# PT4115-Driver.net
KiCad netlist of a schematic drawn in EAGLE
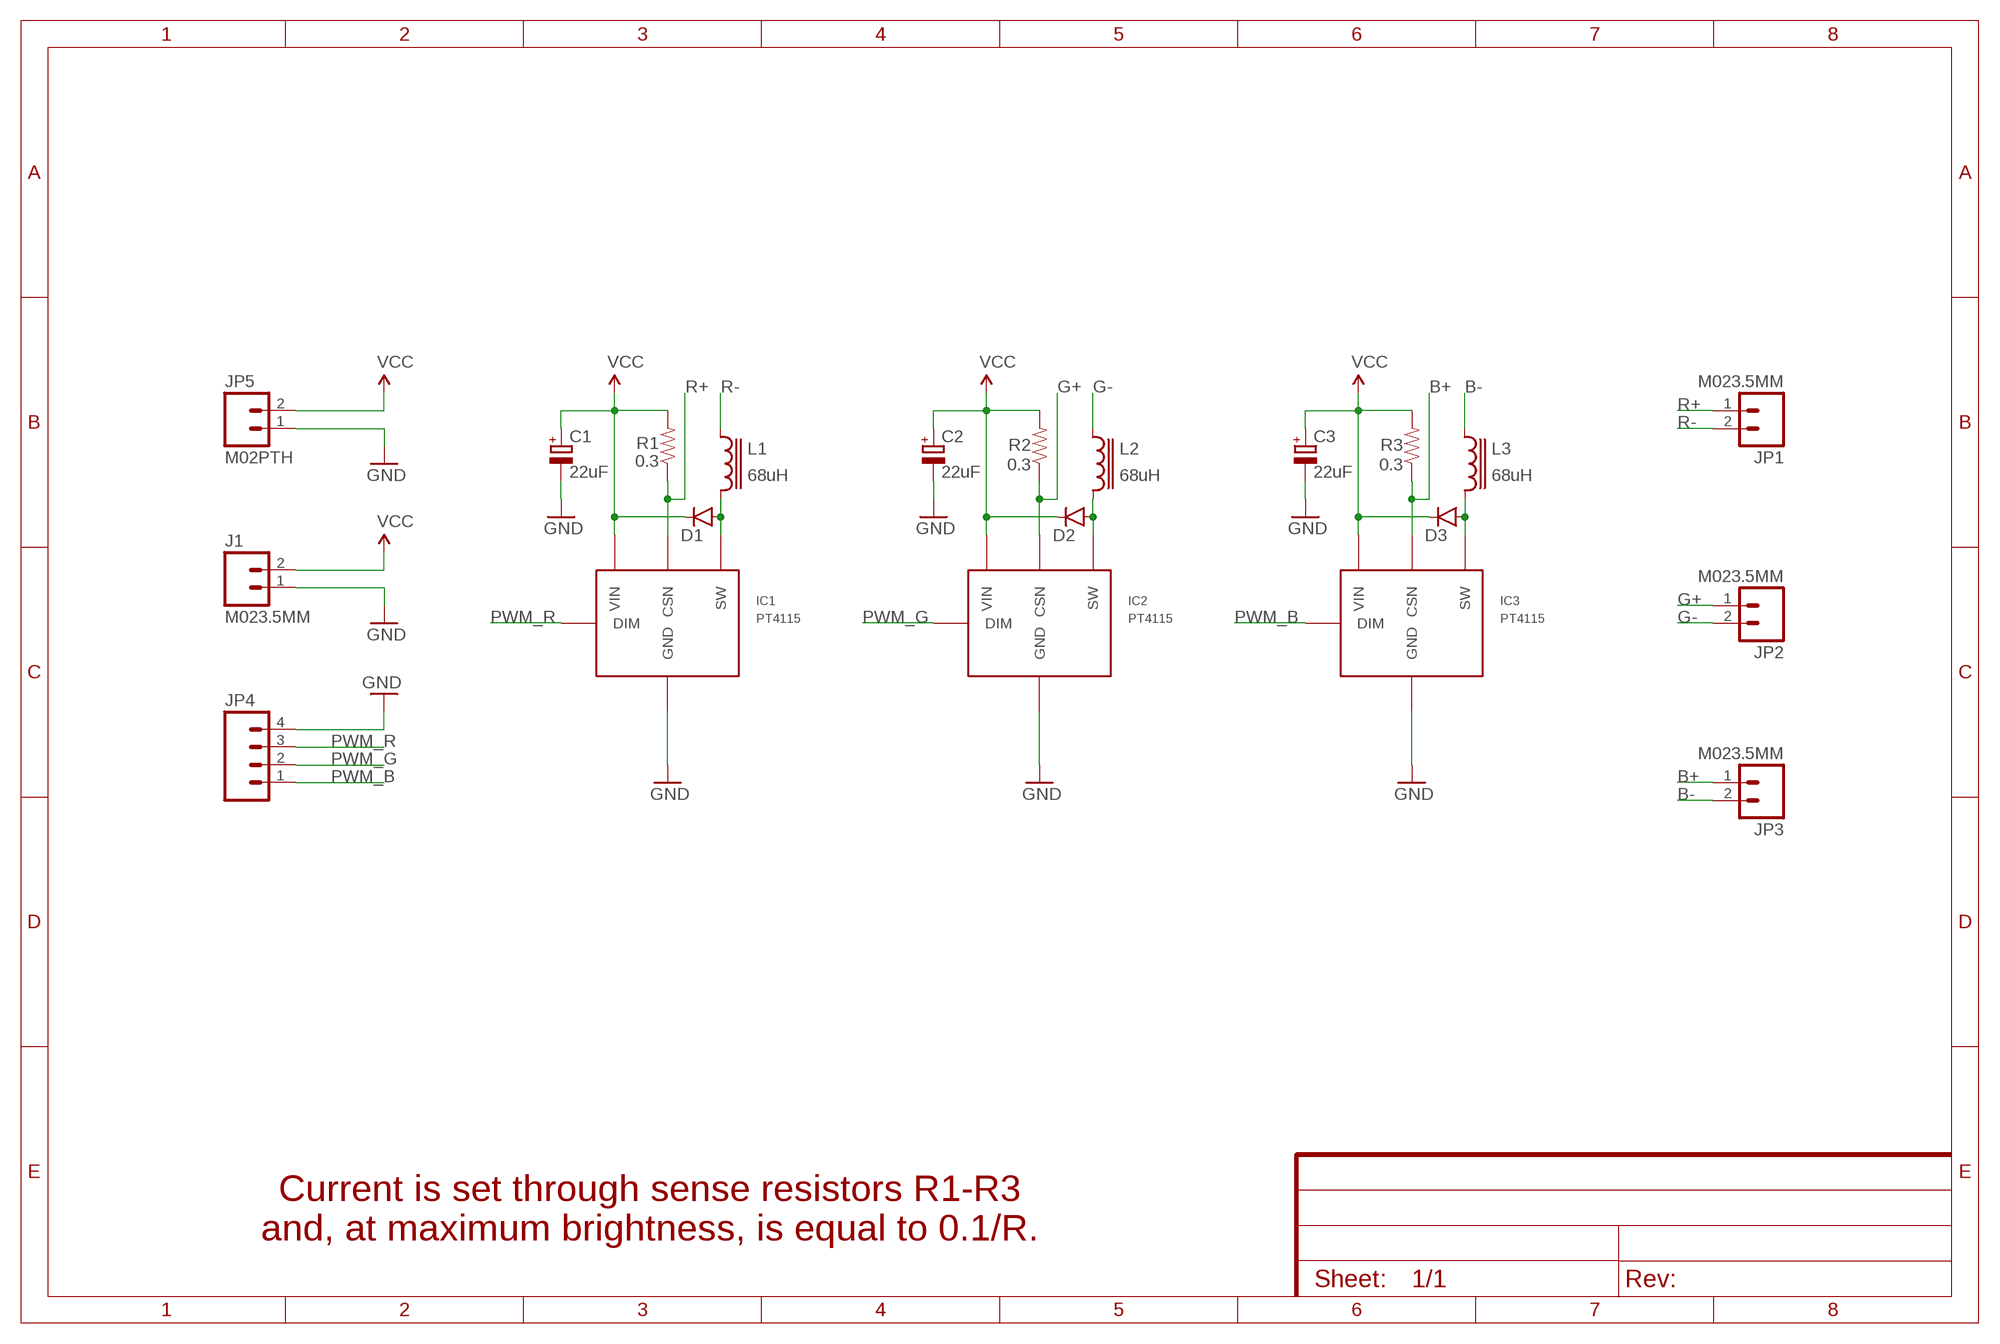
[diagram p0: schematic, sheet 1]

(export (version "E")
  (design (tool "Eeschema 10.0.6"))
  (components
    (comp (ref "C1")
      (value "22uF")
      (footprint "eagle-import:D_7343-31R")
      (libsource (lib "eagle-import") (part "CPOL-EUD/7343-31R"))
    )
    (comp (ref "C2")
      (value "22uF")
      (footprint "eagle-import:D_7343-31R")
      (libsource (lib "eagle-import") (part "CPOL-EUD/7343-31R"))
    )
    (comp (ref "C3")
      (value "22uF")
      (footprint "eagle-import:D_7343-31R")
      (libsource (lib "eagle-import") (part "CPOL-EUD/7343-31R"))
    )
    (comp (ref "D1")
      (value "DIODESMA-KIT")
      (footprint "eagle-import:SMA-DIODE-KIT")
      (libsource (lib "eagle-import") (part "DIODESMA-KIT"))
    )
    (comp (ref "D2")
      (value "DIODESMA-KIT")
      (footprint "eagle-import:SMA-DIODE-KIT")
      (libsource (lib "eagle-import") (part "DIODESMA-KIT"))
    )
    (comp (ref "D3")
      (value "DIODESMA-KIT")
      (footprint "eagle-import:SMA-DIODE-KIT")
      (libsource (lib "eagle-import") (part "DIODESMA-KIT"))
    )
    (comp (ref "IC1")
      (value "PT4115")
      (footprint "eagle-import:PT4115")
      (libsource (lib "eagle-import") (part "PT4115"))
    )
    (comp (ref "IC2")
      (value "PT4115")
      (footprint "eagle-import:PT4115")
      (libsource (lib "eagle-import") (part "PT4115"))
    )
    (comp (ref "IC3")
      (value "PT4115")
      (footprint "eagle-import:PT4115")
      (libsource (lib "eagle-import") (part "PT4115"))
    )
    (comp (ref "J1")
      (value "M023.5MM")
      (footprint "eagle-import:SCREWTERMINAL-3.5MM-2")
      (libsource (lib "eagle-import") (part "M023.5MM"))
    )
    (comp (ref "JP1")
      (value "M023.5MM")
      (footprint "eagle-import:SCREWTERMINAL-3.5MM-2")
      (libsource (lib "eagle-import") (part "M023.5MM"))
    )
    (comp (ref "JP2")
      (value "M023.5MM")
      (footprint "eagle-import:SCREWTERMINAL-3.5MM-2")
      (libsource (lib "eagle-import") (part "M023.5MM"))
    )
    (comp (ref "JP3")
      (value "M023.5MM")
      (footprint "eagle-import:SCREWTERMINAL-3.5MM-2")
      (libsource (lib "eagle-import") (part "M023.5MM"))
    )
    (comp (ref "JP4")
      (value "M04LONGPADS")
      (footprint "eagle-import:1X04_LONGPADS")
      (libsource (lib "eagle-import") (part "M04LONGPADS"))
    )
    (comp (ref "JP5")
      (value "M02PTH")
      (footprint "eagle-import:1X02")
      (libsource (lib "eagle-import") (part "M02PTH"))
    )
    (comp (ref "L1")
      (value "68uH")
      (footprint "eagle-import:ELL6")
      (libsource (lib "eagle-import") (part "ELL6"))
    )
    (comp (ref "L2")
      (value "68uH")
      (footprint "eagle-import:ELL6")
      (libsource (lib "eagle-import") (part "ELL6"))
    )
    (comp (ref "L3")
      (value "68uH")
      (footprint "eagle-import:ELL6")
      (libsource (lib "eagle-import") (part "ELL6"))
    )
    (comp (ref "R1")
      (value "0.3")
      (footprint "eagle-import:0805")
      (libsource (lib "eagle-import") (part "0.3OHM-1/8W-1%(0805)"))
    )
    (comp (ref "R2")
      (value "0.3")
      (footprint "eagle-import:0805")
      (libsource (lib "eagle-import") (part "0.3OHM-1/8W-1%(0805)"))
    )
    (comp (ref "R3")
      (value "0.3")
      (footprint "eagle-import:0805")
      (libsource (lib "eagle-import") (part "0.3OHM-1/8W-1%(0805)"))
    )
  )
  (nets
    (net (code "1") (name "/B+") (class "Default")
      (node (ref "IC3") (pin "4") (pinfunction "CSN_4") (pintype "bidirectional"))
      (node (ref "JP3") (pin "1") (pinfunction "1_1") (pintype "passive"))
      (node (ref "R3") (pin "1") (pinfunction "1_1") (pintype "passive"))
    )
    (net (code "2") (name "/B-") (class "Default")
      (node (ref "JP3") (pin "2") (pinfunction "2_2") (pintype "passive"))
      (node (ref "L3") (pin "1") (pinfunction "1_1") (pintype "passive"))
    )
    (net (code "3") (name "/G+") (class "Default")
      (node (ref "IC2") (pin "4") (pinfunction "CSN_4") (pintype "bidirectional"))
      (node (ref "JP2") (pin "1") (pinfunction "1_1") (pintype "passive"))
      (node (ref "R2") (pin "1") (pinfunction "1_1") (pintype "passive"))
    )
    (net (code "4") (name "/G-") (class "Default")
      (node (ref "JP2") (pin "2") (pinfunction "2_2") (pintype "passive"))
      (node (ref "L2") (pin "1") (pinfunction "1_1") (pintype "passive"))
    )
    (net (code "5") (name "/PWM_B") (class "Default")
      (node (ref "IC3") (pin "3") (pinfunction "DIM_3") (pintype "bidirectional"))
      (node (ref "JP4") (pin "1") (pinfunction "1_1") (pintype "passive"))
    )
    (net (code "6") (name "/PWM_G") (class "Default")
      (node (ref "IC2") (pin "3") (pinfunction "DIM_3") (pintype "bidirectional"))
      (node (ref "JP4") (pin "2") (pinfunction "2_2") (pintype "passive"))
    )
    (net (code "7") (name "/PWM_R") (class "Default")
      (node (ref "IC1") (pin "3") (pinfunction "DIM_3") (pintype "bidirectional"))
      (node (ref "JP4") (pin "3") (pinfunction "3_3") (pintype "passive"))
    )
    (net (code "8") (name "/R+") (class "Default")
      (node (ref "IC1") (pin "4") (pinfunction "CSN_4") (pintype "bidirectional"))
      (node (ref "JP1") (pin "1") (pinfunction "1_1") (pintype "passive"))
      (node (ref "R1") (pin "1") (pinfunction "1_1") (pintype "passive"))
    )
    (net (code "9") (name "/R-") (class "Default")
      (node (ref "JP1") (pin "2") (pinfunction "2_2") (pintype "passive"))
      (node (ref "L1") (pin "1") (pinfunction "1_1") (pintype "passive"))
    )
    (net (code "10") (name "GND") (class "Default")
      (node (ref "C1") (pin "-") (pinfunction "-_-") (pintype "passive"))
      (node (ref "C2") (pin "-") (pinfunction "-_-") (pintype "passive"))
      (node (ref "C3") (pin "-") (pinfunction "-_-") (pintype "passive"))
      (node (ref "IC1") (pin "2") (pinfunction "GND_2") (pintype "power_in"))
      (node (ref "IC1") (pin "2A") (pinfunction "GND_2A") (pintype "power_in"))
      (node (ref "IC2") (pin "2") (pinfunction "GND_2") (pintype "power_in"))
      (node (ref "IC2") (pin "2A") (pinfunction "GND_2A") (pintype "power_in"))
      (node (ref "IC3") (pin "2") (pinfunction "GND_2") (pintype "power_in"))
      (node (ref "IC3") (pin "2A") (pinfunction "GND_2A") (pintype "power_in"))
      (node (ref "J1") (pin "1") (pinfunction "1_1") (pintype "passive"))
      (node (ref "JP4") (pin "4") (pinfunction "4_4") (pintype "passive"))
      (node (ref "JP5") (pin "1") (pinfunction "1_1") (pintype "passive"))
    )
    (net (code "11") (name "Net-(IC1-SW)") (class "Default")
      (node (ref "D1") (pin "A") (pinfunction "A_A") (pintype "passive"))
      (node (ref "IC1") (pin "1") (pinfunction "SW_1") (pintype "bidirectional"))
      (node (ref "L1") (pin "2") (pinfunction "2_2") (pintype "passive"))
    )
    (net (code "12") (name "Net-(IC2-SW)") (class "Default")
      (node (ref "D2") (pin "A") (pinfunction "A_A") (pintype "passive"))
      (node (ref "IC2") (pin "1") (pinfunction "SW_1") (pintype "bidirectional"))
      (node (ref "L2") (pin "2") (pinfunction "2_2") (pintype "passive"))
    )
    (net (code "13") (name "Net-(IC3-SW)") (class "Default")
      (node (ref "D3") (pin "A") (pinfunction "A_A") (pintype "passive"))
      (node (ref "IC3") (pin "1") (pinfunction "SW_1") (pintype "bidirectional"))
      (node (ref "L3") (pin "2") (pinfunction "2_2") (pintype "passive"))
    )
    (net (code "14") (name "VCC") (class "Default")
      (node (ref "C1") (pin "+") (pinfunction "+_+") (pintype "passive"))
      (node (ref "C2") (pin "+") (pinfunction "+_+") (pintype "passive"))
      (node (ref "C3") (pin "+") (pinfunction "+_+") (pintype "passive"))
      (node (ref "D1") (pin "C") (pinfunction "C_C") (pintype "passive"))
      (node (ref "D2") (pin "C") (pinfunction "C_C") (pintype "passive"))
      (node (ref "D3") (pin "C") (pinfunction "C_C") (pintype "passive"))
      (node (ref "IC1") (pin "5") (pinfunction "VIN_5") (pintype "bidirectional"))
      (node (ref "IC2") (pin "5") (pinfunction "VIN_5") (pintype "bidirectional"))
      (node (ref "IC3") (pin "5") (pinfunction "VIN_5") (pintype "bidirectional"))
      (node (ref "J1") (pin "2") (pinfunction "2_2") (pintype "passive"))
      (node (ref "JP5") (pin "2") (pinfunction "2_2") (pintype "passive"))
      (node (ref "R1") (pin "2") (pinfunction "2_2") (pintype "passive"))
      (node (ref "R2") (pin "2") (pinfunction "2_2") (pintype "passive"))
      (node (ref "R3") (pin "2") (pinfunction "2_2") (pintype "passive"))
    )
  )
)
